# Main_MCU.net
KiCad netlist of a schematic drawn in Altium Designer
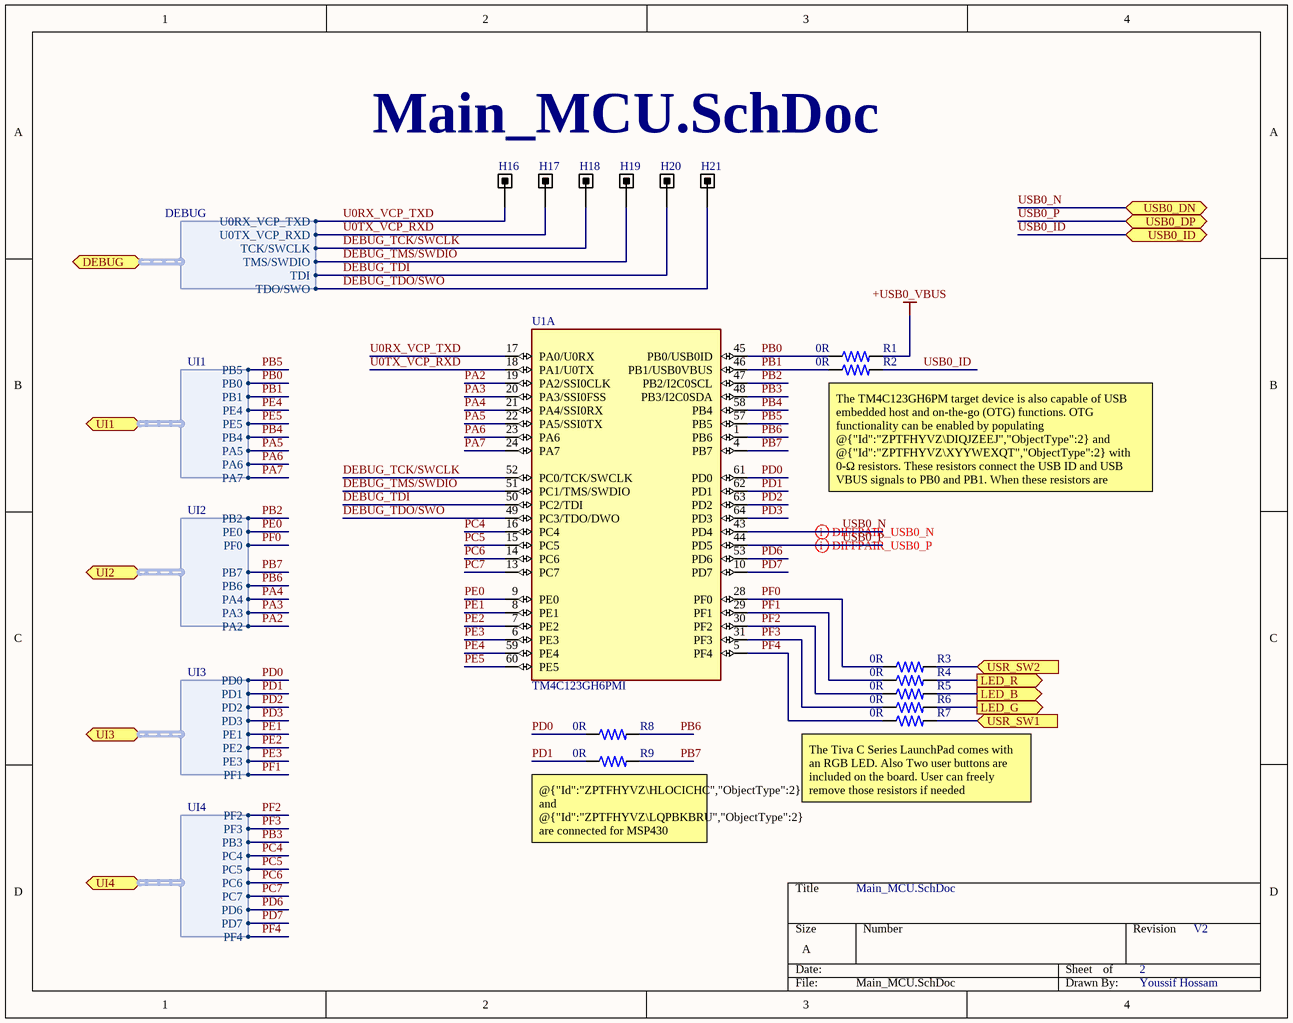
[diagram p0: Main_MCU.SchDoc]

(export (version "E")
  (design (tool "Eeschema 10.0.6"))
  (components
    (comp (ref "H16")
      (value "Test Point")
      (footprint "Test Point")
      (libsource (lib "Integrated_Library") (part "Test Point"))
    )
    (comp (ref "H17")
      (value "Test Point")
      (footprint "Test Point")
      (libsource (lib "Integrated_Library") (part "Test Point"))
    )
    (comp (ref "H18")
      (value "Test Point")
      (footprint "Test Point")
      (libsource (lib "Integrated_Library") (part "Test Point"))
    )
    (comp (ref "H19")
      (value "Test Point")
      (footprint "Test Point")
      (libsource (lib "Integrated_Library") (part "Test Point"))
    )
    (comp (ref "H20")
      (value "Test Point")
      (footprint "Test Point")
      (libsource (lib "Integrated_Library") (part "Test Point"))
    )
    (comp (ref "H21")
      (value "Test Point")
      (footprint "Test Point")
      (libsource (lib "Integrated_Library") (part "Test Point"))
    )
    (comp (ref "R1")
      (value "0R")
      (footprint "FP-ERA3A-IPC_B")
      (description "Fixed Resistor, Metal Glaze/thick Film, 0.1W, 0ohm, Surface Mount, 0603")
      (fields
        (field (name "MANUFACTURER") "Panasonic")
        (field (name "MANUFACTURER PART NUMBER") "ERJ-3GEY0R00V")
      )
      (libsource (lib "Integrated_Library") (part "0603 SMD RES"))
    )
    (comp (ref "R2")
      (value "0R")
      (footprint "FP-ERA3A-IPC_B")
      (description "Fixed Resistor, Metal Glaze/thick Film, 0.1W, 0ohm, Surface Mount, 0603")
      (fields
        (field (name "MANUFACTURER") "Panasonic")
        (field (name "MANUFACTURER PART NUMBER") "ERJ-3GEY0R00V")
      )
      (libsource (lib "Integrated_Library") (part "0603 SMD RES"))
    )
    (comp (ref "R3")
      (value "0R")
      (footprint "FP-ERA3A-IPC_B")
      (description "Fixed Resistor, Metal Glaze/thick Film, 0.1W, 0ohm, Surface Mount, 0603")
      (fields
        (field (name "MANUFACTURER") "Panasonic")
        (field (name "MANUFACTURER PART NUMBER") "ERJ-3GEY0R00V")
      )
      (libsource (lib "Integrated_Library") (part "0603 SMD RES"))
    )
    (comp (ref "R4")
      (value "0R")
      (footprint "FP-ERA3A-IPC_B")
      (description "Fixed Resistor, Metal Glaze/thick Film, 0.1W, 0ohm, Surface Mount, 0603")
      (fields
        (field (name "MANUFACTURER") "Panasonic")
        (field (name "MANUFACTURER PART NUMBER") "ERJ-3GEY0R00V")
      )
      (libsource (lib "Integrated_Library") (part "0603 SMD RES"))
    )
    (comp (ref "R5")
      (value "0R")
      (footprint "FP-ERA3A-IPC_B")
      (description "Fixed Resistor, Metal Glaze/thick Film, 0.1W, 0ohm, Surface Mount, 0603")
      (fields
        (field (name "MANUFACTURER") "Panasonic")
        (field (name "MANUFACTURER PART NUMBER") "ERJ-3GEY0R00V")
      )
      (libsource (lib "Integrated_Library") (part "0603 SMD RES"))
    )
    (comp (ref "R6")
      (value "0R")
      (footprint "FP-ERA3A-IPC_B")
      (description "Fixed Resistor, Metal Glaze/thick Film, 0.1W, 0ohm, Surface Mount, 0603")
      (fields
        (field (name "MANUFACTURER") "Panasonic")
        (field (name "MANUFACTURER PART NUMBER") "ERJ-3GEY0R00V")
      )
      (libsource (lib "Integrated_Library") (part "0603 SMD RES"))
    )
    (comp (ref "R7")
      (value "0R")
      (footprint "FP-ERA3A-IPC_B")
      (description "Fixed Resistor, Metal Glaze/thick Film, 0.1W, 0ohm, Surface Mount, 0603")
      (fields
        (field (name "MANUFACTURER") "Panasonic")
        (field (name "MANUFACTURER PART NUMBER") "ERJ-3GEY0R00V")
      )
      (libsource (lib "Integrated_Library") (part "0603 SMD RES"))
    )
    (comp (ref "R8")
      (value "0R")
      (footprint "0402 RES")
      (description "Metal Glaze/thick Film, 0.0625W, 0ohm, Surface Mount, 0402")
      (fields
        (field (name "MANUFACTURER") "Yageo")
        (field (name "MANUFACTURER PART NUMBER") "RC0402JR-070RL")
      )
      (libsource (lib "Integrated_Library") (part "0402 SMD Resistor"))
    )
    (comp (ref "R9")
      (value "0R")
      (footprint "0402 RES")
      (description "Metal Glaze/thick Film, 0.0625W, 0ohm, Surface Mount, 0402")
      (fields
        (field (name "MANUFACTURER") "Yageo")
        (field (name "MANUFACTURER PART NUMBER") "RC0402JR-070RL")
      )
      (libsource (lib "Integrated_Library") (part "0402 SMD Resistor"))
    )
    (comp (ref "U1")
      (value "TM4C123GH6PMI")
      (footprint "QFP50P1200X1200X160-64N")
      (fields (field (name "MF") "Texas Instruments"))
      (libsource (lib "Integrated_Library") (part "TM4C123GH6PMI"))
    )
  )
  (nets
    (net (code "6") (name "+USB0_VBUS") (class "Default")
      (node (ref "R1") (pin "2") (pinfunction "2_2") (pintype "passive"))
    )
    (net (code "7") (name "/DEBUG_TCK{slash}SWCLK") (class "Default")
      (node (ref "H18") (pin "1") (pinfunction "1_1") (pintype "passive"))
      (node (ref "U1") (pin "52") (pinfunction "PC0/TCK/SWCLK_52") (pintype "bidirectional"))
    )
    (net (code "8") (name "/DEBUG_TDI") (class "Default")
      (node (ref "H20") (pin "1") (pinfunction "1_1") (pintype "passive"))
      (node (ref "U1") (pin "50") (pinfunction "PC2/TDI_50") (pintype "bidirectional"))
    )
    (net (code "9") (name "/DEBUG_TDO{slash}SWO") (class "Default")
      (node (ref "H21") (pin "1") (pinfunction "1_1") (pintype "passive"))
      (node (ref "U1") (pin "49") (pinfunction "PC3/TDO/DWO_49") (pintype "bidirectional"))
    )
    (net (code "10") (name "/DEBUG_TMS{slash}SWDIO") (class "Default")
      (node (ref "H19") (pin "1") (pinfunction "1_1") (pintype "passive"))
      (node (ref "U1") (pin "51") (pinfunction "PC1/TMS/SWDIO_51") (pintype "bidirectional"))
    )
    (net (code "11") (name "/LED_B") (class "Default")
      (node (ref "R5") (pin "2") (pinfunction "2_2") (pintype "passive"))
    )
    (net (code "12") (name "/LED_G") (class "Default")
      (node (ref "R6") (pin "2") (pinfunction "2_2") (pintype "passive"))
    )
    (net (code "13") (name "/LED_R") (class "Default")
      (node (ref "R4") (pin "2") (pinfunction "2_2") (pintype "passive"))
    )
    (net (code "14") (name "/PA2") (class "Default")
      (node (ref "U1") (pin "19") (pinfunction "PA2/SSI0CLK_19") (pintype "bidirectional"))
    )
    (net (code "15") (name "/PA3") (class "Default")
      (node (ref "U1") (pin "20") (pinfunction "PA3/SSI0FSS_20") (pintype "bidirectional"))
    )
    (net (code "16") (name "/PA4") (class "Default")
      (node (ref "U1") (pin "21") (pinfunction "PA4/SSI0RX_21") (pintype "bidirectional"))
    )
    (net (code "17") (name "/PA5") (class "Default")
      (node (ref "U1") (pin "22") (pinfunction "PA5/SSI0TX_22") (pintype "bidirectional"))
    )
    (net (code "18") (name "/PA6") (class "Default")
      (node (ref "U1") (pin "23") (pinfunction "PA6_23") (pintype "bidirectional"))
    )
    (net (code "19") (name "/PA7") (class "Default")
      (node (ref "U1") (pin "24") (pinfunction "PA7_24") (pintype "bidirectional"))
    )
    (net (code "20") (name "/PB0") (class "Default")
      (node (ref "R1") (pin "1") (pinfunction "1_1") (pintype "passive"))
      (node (ref "U1") (pin "45") (pinfunction "PB0/USB0ID_45") (pintype "bidirectional"))
    )
    (net (code "21") (name "/PB1") (class "Default")
      (node (ref "R2") (pin "1") (pinfunction "1_1") (pintype "passive"))
      (node (ref "U1") (pin "46") (pinfunction "PB1/USB0VBUS_46") (pintype "bidirectional"))
    )
    (net (code "22") (name "/PB2") (class "Default")
      (node (ref "U1") (pin "47") (pinfunction "PB2/I2C0SCL_47") (pintype "bidirectional"))
    )
    (net (code "23") (name "/PB3") (class "Default")
      (node (ref "U1") (pin "48") (pinfunction "PB3/I2C0SDA_48") (pintype "bidirectional"))
    )
    (net (code "24") (name "/PB4") (class "Default")
      (node (ref "U1") (pin "58") (pinfunction "PB4_58") (pintype "bidirectional"))
    )
    (net (code "25") (name "/PB5") (class "Default")
      (node (ref "U1") (pin "57") (pinfunction "PB5_57") (pintype "bidirectional"))
    )
    (net (code "26") (name "/PB6") (class "Default")
      (node (ref "R8") (pin "2") (pinfunction "2_2") (pintype "passive"))
      (node (ref "U1") (pin "1") (pinfunction "PB6_1") (pintype "bidirectional"))
    )
    (net (code "27") (name "/PB7") (class "Default")
      (node (ref "R9") (pin "2") (pinfunction "2_2") (pintype "passive"))
      (node (ref "U1") (pin "4") (pinfunction "PB7_4") (pintype "bidirectional"))
    )
    (net (code "28") (name "/PC4") (class "Default")
      (node (ref "U1") (pin "16") (pinfunction "PC4_16") (pintype "bidirectional"))
    )
    (net (code "29") (name "/PC5") (class "Default")
      (node (ref "U1") (pin "15") (pinfunction "PC5_15") (pintype "bidirectional"))
    )
    (net (code "30") (name "/PC6") (class "Default")
      (node (ref "U1") (pin "14") (pinfunction "PC6_14") (pintype "bidirectional"))
    )
    (net (code "31") (name "/PC7") (class "Default")
      (node (ref "U1") (pin "13") (pinfunction "PC7_13") (pintype "bidirectional"))
    )
    (net (code "32") (name "/PD0") (class "Default")
      (node (ref "R8") (pin "1") (pinfunction "1_1") (pintype "passive"))
      (node (ref "U1") (pin "61") (pinfunction "PD0_61") (pintype "bidirectional"))
    )
    (net (code "33") (name "/PD1") (class "Default")
      (node (ref "R9") (pin "1") (pinfunction "1_1") (pintype "passive"))
      (node (ref "U1") (pin "62") (pinfunction "PD1_62") (pintype "bidirectional"))
    )
    (net (code "34") (name "/PD2") (class "Default")
      (node (ref "U1") (pin "63") (pinfunction "PD2_63") (pintype "bidirectional"))
    )
    (net (code "35") (name "/PD3") (class "Default")
      (node (ref "U1") (pin "64") (pinfunction "PD3_64") (pintype "bidirectional"))
    )
    (net (code "36") (name "/PD6") (class "Default")
      (node (ref "U1") (pin "53") (pinfunction "PD6_53") (pintype "bidirectional"))
    )
    (net (code "37") (name "/PD7") (class "Default")
      (node (ref "U1") (pin "10") (pinfunction "PD7_10") (pintype "bidirectional"))
    )
    (net (code "38") (name "/PE0") (class "Default")
      (node (ref "U1") (pin "9") (pinfunction "PE0_9") (pintype "bidirectional"))
    )
    (net (code "39") (name "/PE1") (class "Default")
      (node (ref "U1") (pin "8") (pinfunction "PE1_8") (pintype "bidirectional"))
    )
    (net (code "40") (name "/PE2") (class "Default")
      (node (ref "U1") (pin "7") (pinfunction "PE2_7") (pintype "bidirectional"))
    )
    (net (code "41") (name "/PE3") (class "Default")
      (node (ref "U1") (pin "6") (pinfunction "PE3_6") (pintype "bidirectional"))
    )
    (net (code "42") (name "/PE4") (class "Default")
      (node (ref "U1") (pin "59") (pinfunction "PE4_59") (pintype "bidirectional"))
    )
    (net (code "43") (name "/PE5") (class "Default")
      (node (ref "U1") (pin "60") (pinfunction "PE5_60") (pintype "bidirectional"))
    )
    (net (code "44") (name "/PF0") (class "Default")
      (node (ref "R3") (pin "1") (pinfunction "1_1") (pintype "passive"))
      (node (ref "U1") (pin "28") (pinfunction "PF0_28") (pintype "bidirectional"))
    )
    (net (code "45") (name "/PF1") (class "Default")
      (node (ref "R4") (pin "1") (pinfunction "1_1") (pintype "passive"))
      (node (ref "U1") (pin "29") (pinfunction "PF1_29") (pintype "bidirectional"))
    )
    (net (code "46") (name "/PF2") (class "Default")
      (node (ref "R5") (pin "1") (pinfunction "1_1") (pintype "passive"))
      (node (ref "U1") (pin "30") (pinfunction "PF2_30") (pintype "bidirectional"))
    )
    (net (code "47") (name "/PF3") (class "Default")
      (node (ref "R6") (pin "1") (pinfunction "1_1") (pintype "passive"))
      (node (ref "U1") (pin "31") (pinfunction "PF3_31") (pintype "bidirectional"))
    )
    (net (code "48") (name "/PF4") (class "Default")
      (node (ref "R7") (pin "1") (pinfunction "1_1") (pintype "passive"))
      (node (ref "U1") (pin "5") (pinfunction "PF4_5") (pintype "bidirectional"))
    )
    (net (code "49") (name "/U0RX_VCP_TXD") (class "Default")
      (node (ref "H16") (pin "1") (pinfunction "1_1") (pintype "passive"))
      (node (ref "U1") (pin "17") (pinfunction "PA0/U0RX_17") (pintype "bidirectional"))
    )
    (net (code "50") (name "/U0TX_VCP_RXD") (class "Default")
      (node (ref "H17") (pin "1") (pinfunction "1_1") (pintype "passive"))
      (node (ref "U1") (pin "18") (pinfunction "PA1/U0TX_18") (pintype "bidirectional"))
    )
    (net (code "51") (name "/USB0_ID") (class "Default")
      (node (ref "R2") (pin "2") (pinfunction "2_2") (pintype "passive"))
    )
    (net (code "52") (name "/USB0_N") (class "Default")
      (node (ref "U1") (pin "43") (pinfunction "PD4_43") (pintype "bidirectional"))
    )
    (net (code "53") (name "/USB0_P") (class "Default")
      (node (ref "U1") (pin "44") (pinfunction "PD5_44") (pintype "bidirectional"))
    )
    (net (code "54") (name "/USR_SW1") (class "Default")
      (node (ref "R7") (pin "2") (pinfunction "2_2") (pintype "passive"))
    )
    (net (code "55") (name "/USR_SW2") (class "Default")
      (node (ref "R3") (pin "2") (pinfunction "2_2") (pintype "passive"))
    )
  )
)
